# NFC_Access_CPU1_R00.net
KiCad netlist of a schematic drawn in Altium Designer
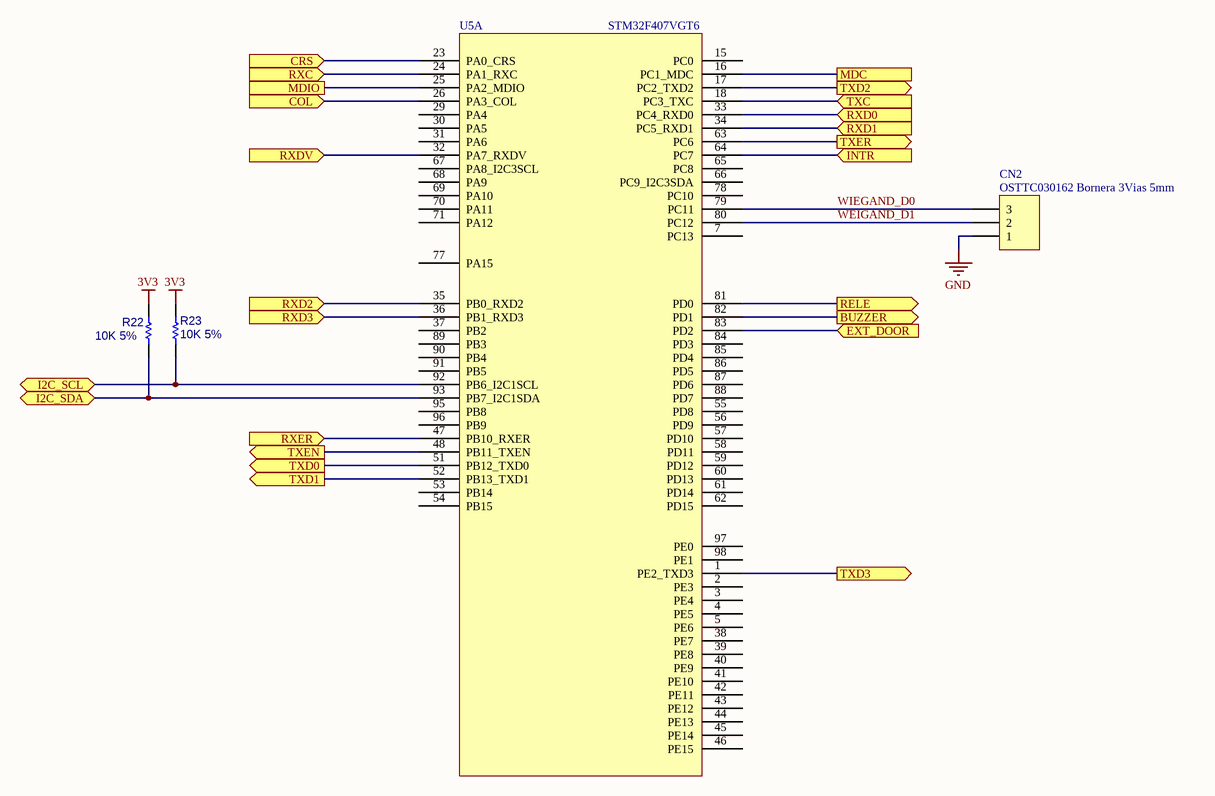
[diagram p0: NFC_Access_CPU1_R00.SchDoc]

(export (version "E")
  (design (tool "Eeschema 10.0.6"))
  (components
    (comp (ref "CN2")
      (value "OSTTC030162 Bornera 3Vias 5mm")
      (footprint "TerminalBlock_1x3_P5mm")
      (description "TERM BLK 3POS SIDE ENTRY 5MM PCB\r\nED2601-ND")
      (libsource (lib "WiFiNode_R00") (part "CONN_03P"))
    )
    (comp (ref "R22")
      (value "10K 5%")
      (footprint "R_0603")
      (description "Resistor\r\nCR0603-JW-103ELFTR-ND")
      (libsource (lib "NFC_Access_Lib") (part "Res1"))
    )
    (comp (ref "R23")
      (value "10K 5%")
      (footprint "R_0603")
      (description "Resistor\r\nCR0603-JW-103ELFTR-ND")
      (libsource (lib "NFC_Access_Lib") (part "Res1"))
    )
    (comp (ref "U5")
      (value "STM32F407VGT6")
      (footprint "LQFP100")
      (description "Cortex M4 32bit CPU\r\n497-11605-ND")
      (libsource (lib "NFC_Access_Lib") (part "STM32F407"))
    )
  )
  (nets
    (net (code "1") (name "/BUZZER") (class "Default")
      (node (ref "U5") (pin "82") (pinfunction "PD1_82") (pintype "passive"))
    )
    (net (code "2") (name "/COL") (class "Default")
      (node (ref "U5") (pin "26") (pinfunction "PA3_COL_26") (pintype "passive"))
    )
    (net (code "3") (name "/CRS") (class "Default")
      (node (ref "U5") (pin "23") (pinfunction "PA0_CRS_23") (pintype "passive"))
    )
    (net (code "4") (name "/EXT_DOOR") (class "Default")
      (node (ref "U5") (pin "83") (pinfunction "PD2_83") (pintype "passive"))
    )
    (net (code "5") (name "/I2C_SCL") (class "Default")
      (node (ref "R23") (pin "1") (pinfunction "1_1") (pintype "passive"))
      (node (ref "U5") (pin "92") (pinfunction "PB6_I2C1SCL_92") (pintype "passive"))
    )
    (net (code "6") (name "/I2C_SDA") (class "Default")
      (node (ref "R22") (pin "1") (pinfunction "1_1") (pintype "passive"))
      (node (ref "U5") (pin "93") (pinfunction "PB7_I2C1SDA_93") (pintype "passive"))
    )
    (net (code "7") (name "/INTR") (class "Default")
      (node (ref "U5") (pin "64") (pinfunction "PC7_64") (pintype "passive"))
    )
    (net (code "8") (name "/MDC") (class "Default")
      (node (ref "U5") (pin "16") (pinfunction "PC1_MDC_16") (pintype "passive"))
    )
    (net (code "9") (name "/MDIO") (class "Default")
      (node (ref "U5") (pin "25") (pinfunction "PA2_MDIO_25") (pintype "passive"))
    )
    (net (code "10") (name "/RELE") (class "Default")
      (node (ref "U5") (pin "81") (pinfunction "PD0_81") (pintype "passive"))
    )
    (net (code "11") (name "/RXC") (class "Default")
      (node (ref "U5") (pin "24") (pinfunction "PA1_RXC_24") (pintype "passive"))
    )
    (net (code "12") (name "/RXD0") (class "Default")
      (node (ref "U5") (pin "33") (pinfunction "PC4_RXD0_33") (pintype "passive"))
    )
    (net (code "13") (name "/RXD1") (class "Default")
      (node (ref "U5") (pin "34") (pinfunction "PC5_RXD1_34") (pintype "passive"))
    )
    (net (code "14") (name "/RXD2") (class "Default")
      (node (ref "U5") (pin "35") (pinfunction "PB0_RXD2_35") (pintype "passive"))
    )
    (net (code "15") (name "/RXD3") (class "Default")
      (node (ref "U5") (pin "36") (pinfunction "PB1_RXD3_36") (pintype "passive"))
    )
    (net (code "16") (name "/RXDV") (class "Default")
      (node (ref "U5") (pin "32") (pinfunction "PA7_RXDV_32") (pintype "passive"))
    )
    (net (code "17") (name "/RXER") (class "Default")
      (node (ref "U5") (pin "47") (pinfunction "PB10_RXER_47") (pintype "passive"))
    )
    (net (code "18") (name "/TXC") (class "Default")
      (node (ref "U5") (pin "18") (pinfunction "PC3_TXC_18") (pintype "passive"))
    )
    (net (code "19") (name "/TXD0") (class "Default")
      (node (ref "U5") (pin "51") (pinfunction "PB12_TXD0_51") (pintype "passive"))
    )
    (net (code "20") (name "/TXD1") (class "Default")
      (node (ref "U5") (pin "52") (pinfunction "PB13_TXD1_52") (pintype "passive"))
    )
    (net (code "21") (name "/TXD2") (class "Default")
      (node (ref "U5") (pin "17") (pinfunction "PC2_TXD2_17") (pintype "passive"))
    )
    (net (code "22") (name "/TXD3") (class "Default")
      (node (ref "U5") (pin "1") (pinfunction "PE2_TXD3_1") (pintype "passive"))
    )
    (net (code "23") (name "/TXEN") (class "Default")
      (node (ref "U5") (pin "48") (pinfunction "PB11_TXEN_48") (pintype "passive"))
    )
    (net (code "24") (name "/TXER") (class "Default")
      (node (ref "U5") (pin "63") (pinfunction "PC6_63") (pintype "passive"))
    )
    (net (code "25") (name "/WEIGAND_D1") (class "Default")
      (node (ref "CN2") (pin "2") (pinfunction "2_2") (pintype "passive"))
      (node (ref "U5") (pin "80") (pinfunction "PC12_80") (pintype "passive"))
    )
    (net (code "26") (name "/WIEGAND_D0") (class "Default")
      (node (ref "CN2") (pin "3") (pinfunction "3_3") (pintype "passive"))
      (node (ref "U5") (pin "79") (pinfunction "PC11_79") (pintype "passive"))
    )
    (net (code "27") (name "3V3") (class "Default")
      (node (ref "R22") (pin "2") (pinfunction "2_2") (pintype "passive"))
      (node (ref "R23") (pin "2") (pinfunction "2_2") (pintype "passive"))
    )
    (net (code "28") (name "GND") (class "Default")
      (node (ref "CN2") (pin "1") (pinfunction "1_1") (pintype "passive"))
    )
    (net (code "29") (name "unconnected-(U5A-PA4-Pad29)") (class "Default")
      (node (ref "U5") (pin "29") (pinfunction "PA4_29") (pintype "passive"))
    )
    (net (code "30") (name "unconnected-(U5A-PA5-Pad30)") (class "Default")
      (node (ref "U5") (pin "30") (pinfunction "PA5_30") (pintype "passive"))
    )
    (net (code "31") (name "unconnected-(U5A-PA6-Pad31)") (class "Default")
      (node (ref "U5") (pin "31") (pinfunction "PA6_31") (pintype "passive"))
    )
    (net (code "32") (name "unconnected-(U5A-PA8_I2C3SCL-Pad67)") (class "Default")
      (node (ref "U5") (pin "67") (pinfunction "PA8_I2C3SCL_67") (pintype "passive"))
    )
    (net (code "33") (name "unconnected-(U5A-PA9-Pad68)") (class "Default")
      (node (ref "U5") (pin "68") (pinfunction "PA9_68") (pintype "passive"))
    )
    (net (code "34") (name "unconnected-(U5A-PA10-Pad69)") (class "Default")
      (node (ref "U5") (pin "69") (pinfunction "PA10_69") (pintype "passive"))
    )
    (net (code "35") (name "unconnected-(U5A-PA11-Pad70)") (class "Default")
      (node (ref "U5") (pin "70") (pinfunction "PA11_70") (pintype "passive"))
    )
    (net (code "36") (name "unconnected-(U5A-PA12-Pad71)") (class "Default")
      (node (ref "U5") (pin "71") (pinfunction "PA12_71") (pintype "passive"))
    )
    (net (code "37") (name "unconnected-(U5A-PA15-Pad77)") (class "Default")
      (node (ref "U5") (pin "77") (pinfunction "PA15_77") (pintype "passive"))
    )
    (net (code "38") (name "unconnected-(U5A-PB2-Pad37)") (class "Default")
      (node (ref "U5") (pin "37") (pinfunction "PB2_37") (pintype "passive"))
    )
    (net (code "39") (name "unconnected-(U5A-PB3-Pad89)") (class "Default")
      (node (ref "U5") (pin "89") (pinfunction "PB3_89") (pintype "passive"))
    )
    (net (code "40") (name "unconnected-(U5A-PB4-Pad90)") (class "Default")
      (node (ref "U5") (pin "90") (pinfunction "PB4_90") (pintype "passive"))
    )
    (net (code "41") (name "unconnected-(U5A-PB5-Pad91)") (class "Default")
      (node (ref "U5") (pin "91") (pinfunction "PB5_91") (pintype "passive"))
    )
    (net (code "42") (name "unconnected-(U5A-PB8-Pad95)") (class "Default")
      (node (ref "U5") (pin "95") (pinfunction "PB8_95") (pintype "passive"))
    )
    (net (code "43") (name "unconnected-(U5A-PB9-Pad96)") (class "Default")
      (node (ref "U5") (pin "96") (pinfunction "PB9_96") (pintype "passive"))
    )
    (net (code "44") (name "unconnected-(U5A-PB14-Pad53)") (class "Default")
      (node (ref "U5") (pin "53") (pinfunction "PB14_53") (pintype "passive"))
    )
    (net (code "45") (name "unconnected-(U5A-PB15-Pad54)") (class "Default")
      (node (ref "U5") (pin "54") (pinfunction "PB15_54") (pintype "passive"))
    )
    (net (code "46") (name "unconnected-(U5A-PC0-Pad15)") (class "Default")
      (node (ref "U5") (pin "15") (pinfunction "PC0_15") (pintype "passive"))
    )
    (net (code "47") (name "unconnected-(U5A-PC8-Pad65)") (class "Default")
      (node (ref "U5") (pin "65") (pinfunction "PC8_65") (pintype "passive"))
    )
    (net (code "48") (name "unconnected-(U5A-PC9_I2C3SDA-Pad66)") (class "Default")
      (node (ref "U5") (pin "66") (pinfunction "PC9_I2C3SDA_66") (pintype "passive"))
    )
    (net (code "49") (name "unconnected-(U5A-PC10-Pad78)") (class "Default")
      (node (ref "U5") (pin "78") (pinfunction "PC10_78") (pintype "passive"))
    )
    (net (code "50") (name "unconnected-(U5A-PC13-Pad7)") (class "Default")
      (node (ref "U5") (pin "7") (pinfunction "PC13_7") (pintype "passive"))
    )
    (net (code "51") (name "unconnected-(U5A-PD3-Pad84)") (class "Default")
      (node (ref "U5") (pin "84") (pinfunction "PD3_84") (pintype "passive"))
    )
    (net (code "52") (name "unconnected-(U5A-PD4-Pad85)") (class "Default")
      (node (ref "U5") (pin "85") (pinfunction "PD4_85") (pintype "passive"))
    )
    (net (code "53") (name "unconnected-(U5A-PD5-Pad86)") (class "Default")
      (node (ref "U5") (pin "86") (pinfunction "PD5_86") (pintype "passive"))
    )
    (net (code "54") (name "unconnected-(U5A-PD6-Pad87)") (class "Default")
      (node (ref "U5") (pin "87") (pinfunction "PD6_87") (pintype "passive"))
    )
    (net (code "55") (name "unconnected-(U5A-PD7-Pad88)") (class "Default")
      (node (ref "U5") (pin "88") (pinfunction "PD7_88") (pintype "passive"))
    )
    (net (code "56") (name "unconnected-(U5A-PD8-Pad55)") (class "Default")
      (node (ref "U5") (pin "55") (pinfunction "PD8_55") (pintype "passive"))
    )
    (net (code "57") (name "unconnected-(U5A-PD9-Pad56)") (class "Default")
      (node (ref "U5") (pin "56") (pinfunction "PD9_56") (pintype "passive"))
    )
    (net (code "58") (name "unconnected-(U5A-PD10-Pad57)") (class "Default")
      (node (ref "U5") (pin "57") (pinfunction "PD10_57") (pintype "passive"))
    )
    (net (code "59") (name "unconnected-(U5A-PD11-Pad58)") (class "Default")
      (node (ref "U5") (pin "58") (pinfunction "PD11_58") (pintype "passive"))
    )
    (net (code "60") (name "unconnected-(U5A-PD12-Pad59)") (class "Default")
      (node (ref "U5") (pin "59") (pinfunction "PD12_59") (pintype "passive"))
    )
    (net (code "61") (name "unconnected-(U5A-PD13-Pad60)") (class "Default")
      (node (ref "U5") (pin "60") (pinfunction "PD13_60") (pintype "passive"))
    )
    (net (code "62") (name "unconnected-(U5A-PD14-Pad61)") (class "Default")
      (node (ref "U5") (pin "61") (pinfunction "PD14_61") (pintype "passive"))
    )
    (net (code "63") (name "unconnected-(U5A-PD15-Pad62)") (class "Default")
      (node (ref "U5") (pin "62") (pinfunction "PD15_62") (pintype "passive"))
    )
    (net (code "64") (name "unconnected-(U5A-PE0-Pad97)") (class "Default")
      (node (ref "U5") (pin "97") (pinfunction "PE0_97") (pintype "passive"))
    )
    (net (code "65") (name "unconnected-(U5A-PE1-Pad98)") (class "Default")
      (node (ref "U5") (pin "98") (pinfunction "PE1_98") (pintype "passive"))
    )
    (net (code "66") (name "unconnected-(U5A-PE3-Pad2)") (class "Default")
      (node (ref "U5") (pin "2") (pinfunction "PE3_2") (pintype "passive"))
    )
    (net (code "67") (name "unconnected-(U5A-PE4-Pad3)") (class "Default")
      (node (ref "U5") (pin "3") (pinfunction "PE4_3") (pintype "passive"))
    )
    (net (code "68") (name "unconnected-(U5A-PE5-Pad4)") (class "Default")
      (node (ref "U5") (pin "4") (pinfunction "PE5_4") (pintype "passive"))
    )
    (net (code "69") (name "unconnected-(U5A-PE6-Pad5)") (class "Default")
      (node (ref "U5") (pin "5") (pinfunction "PE6_5") (pintype "passive"))
    )
    (net (code "70") (name "unconnected-(U5A-PE7-Pad38)") (class "Default")
      (node (ref "U5") (pin "38") (pinfunction "PE7_38") (pintype "passive"))
    )
    (net (code "71") (name "unconnected-(U5A-PE8-Pad39)") (class "Default")
      (node (ref "U5") (pin "39") (pinfunction "PE8_39") (pintype "passive"))
    )
    (net (code "72") (name "unconnected-(U5A-PE9-Pad40)") (class "Default")
      (node (ref "U5") (pin "40") (pinfunction "PE9_40") (pintype "passive"))
    )
    (net (code "73") (name "unconnected-(U5A-PE10-Pad41)") (class "Default")
      (node (ref "U5") (pin "41") (pinfunction "PE10_41") (pintype "passive"))
    )
    (net (code "74") (name "unconnected-(U5A-PE11-Pad42)") (class "Default")
      (node (ref "U5") (pin "42") (pinfunction "PE11_42") (pintype "passive"))
    )
    (net (code "75") (name "unconnected-(U5A-PE12-Pad43)") (class "Default")
      (node (ref "U5") (pin "43") (pinfunction "PE12_43") (pintype "passive"))
    )
    (net (code "76") (name "unconnected-(U5A-PE13-Pad44)") (class "Default")
      (node (ref "U5") (pin "44") (pinfunction "PE13_44") (pintype "passive"))
    )
    (net (code "77") (name "unconnected-(U5A-PE14-Pad45)") (class "Default")
      (node (ref "U5") (pin "45") (pinfunction "PE14_45") (pintype "passive"))
    )
    (net (code "78") (name "unconnected-(U5A-PE15-Pad46)") (class "Default")
      (node (ref "U5") (pin "46") (pinfunction "PE15_46") (pintype "passive"))
    )
  )
)
